# Portals_Controls.net
KiCad netlist of a schematic drawn in EAGLE
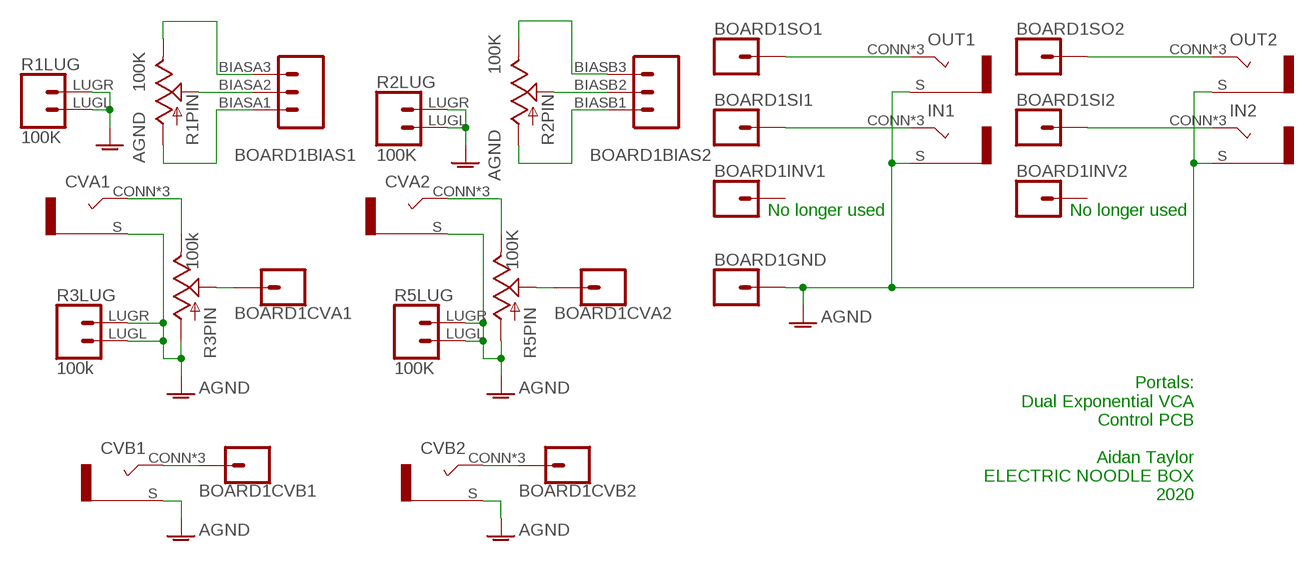
[diagram p0: schematic, sheet 1]

(export (version "E")
  (design (tool "Eeschema 10.0.6"))
  (components
    (comp (ref "BOARD1")
      (value "PORTALS_LINK")
      (footprint "eagle-import:PORTALS")
      (libsource (lib "eagle-import") (part "PORTALS_LINK"))
    )
    (comp (ref "CVA1")
      (value "COMBI-JACKCINCHNANA")
      (footprint "eagle-import:NEWCOMBOJACK_PANEL")
      (libsource (lib "eagle-import") (part "COMBI-JACKCINCHNANA"))
    )
    (comp (ref "CVA2")
      (value "COMBI-JACKCINCHNANA")
      (footprint "eagle-import:NEWCOMBOJACK_PANEL")
      (libsource (lib "eagle-import") (part "COMBI-JACKCINCHNANA"))
    )
    (comp (ref "CVB1")
      (value "COMBI-JACKCINCHNANA")
      (footprint "eagle-import:NEWCOMBOJACK_PANEL")
      (libsource (lib "eagle-import") (part "COMBI-JACKCINCHNANA"))
    )
    (comp (ref "CVB2")
      (value "COMBI-JACKCINCHNANA")
      (footprint "eagle-import:NEWCOMBOJACK_PANEL")
      (libsource (lib "eagle-import") (part "COMBI-JACKCINCHNANA"))
    )
    (comp (ref "IN1")
      (value "COMBI-JACKCINCHNANA")
      (footprint "eagle-import:NEWCOMBOJACK_PANEL")
      (libsource (lib "eagle-import") (part "COMBI-JACKCINCHNANA"))
    )
    (comp (ref "IN2")
      (value "COMBI-JACKCINCHNANA")
      (footprint "eagle-import:NEWCOMBOJACK_PANEL")
      (libsource (lib "eagle-import") (part "COMBI-JACKCINCHNANA"))
    )
    (comp (ref "OUT1")
      (value "COMBI-JACKCINCHNANA")
      (footprint "eagle-import:NEWCOMBOJACK_PANEL")
      (libsource (lib "eagle-import") (part "COMBI-JACKCINCHNANA"))
    )
    (comp (ref "OUT2")
      (value "COMBI-JACKCINCHNANA")
      (footprint "eagle-import:NEWCOMBOJACK_PANEL")
      (libsource (lib "eagle-import") (part "COMBI-JACKCINCHNANA"))
    )
    (comp (ref "R1")
      (value "100K")
      (footprint "eagle-import:ALPHA_RV09_9MMPOT")
      (libsource (lib "eagle-import") (part "POTENTIOMETER"))
    )
    (comp (ref "R2")
      (value "100K")
      (footprint "eagle-import:ALPHA_RV09_9MMPOT")
      (libsource (lib "eagle-import") (part "POTENTIOMETER"))
    )
    (comp (ref "R3")
      (value "100k")
      (footprint "eagle-import:ALPHA_RV09_9MMPOT")
      (libsource (lib "eagle-import") (part "POTENTIOMETER"))
    )
    (comp (ref "R5")
      (value "100K")
      (footprint "eagle-import:ALPHA_RV09_9MMPOT")
      (libsource (lib "eagle-import") (part "POTENTIOMETER"))
    )
  )
  (nets
    (net (code "1") (name "AGND") (class "Default")
      (node (ref "BOARD1") (pin "G1") (pinfunction "1_G1") (pintype "passive"))
      (node (ref "BOARD1") (pin "G2") (pinfunction "1_G2") (pintype "passive"))
      (node (ref "BOARD1") (pin "G3") (pinfunction "1_G3") (pintype "passive"))
      (node (ref "BOARD1") (pin "G4") (pinfunction "1_G4") (pintype "passive"))
      (node (ref "CVA1") (pin "S") (pinfunction "S_S") (pintype "passive"))
      (node (ref "CVA2") (pin "S") (pinfunction "S_S") (pintype "passive"))
      (node (ref "CVB1") (pin "S") (pinfunction "S_S") (pintype "passive"))
      (node (ref "CVB2") (pin "S") (pinfunction "S_S") (pintype "passive"))
      (node (ref "IN1") (pin "S") (pinfunction "S_S") (pintype "passive"))
      (node (ref "IN2") (pin "S") (pinfunction "S_S") (pintype "passive"))
      (node (ref "OUT1") (pin "S") (pinfunction "S_S") (pintype "passive"))
      (node (ref "OUT2") (pin "S") (pinfunction "S_S") (pintype "passive"))
      (node (ref "R1") (pin "LUGL") (pinfunction "1_LUGL") (pintype "passive"))
      (node (ref "R1") (pin "LUGR") (pinfunction "2_LUGR") (pintype "passive"))
      (node (ref "R2") (pin "LUGL") (pinfunction "1_LUGL") (pintype "passive"))
      (node (ref "R2") (pin "LUGR") (pinfunction "2_LUGR") (pintype "passive"))
      (node (ref "R3") (pin "C1") (pinfunction "A_C1") (pintype "passive"))
      (node (ref "R3") (pin "LUGL") (pinfunction "1_LUGL") (pintype "passive"))
      (node (ref "R3") (pin "LUGR") (pinfunction "2_LUGR") (pintype "passive"))
      (node (ref "R5") (pin "C1") (pinfunction "A_C1") (pintype "passive"))
      (node (ref "R5") (pin "LUGL") (pinfunction "1_LUGL") (pintype "passive"))
      (node (ref "R5") (pin "LUGR") (pinfunction "2_LUGR") (pintype "passive"))
    )
    (net (code "2") (name "Net-(BOARD1A-1)") (class "Default")
      (node (ref "BOARD1") (pin "BIASA1") (pinfunction "1_BIASA1") (pintype "passive"))
      (node (ref "R1") (pin "C1") (pinfunction "A_C1") (pintype "passive"))
    )
    (net (code "3") (name "Net-(BOARD1A-2)") (class "Default")
      (node (ref "BOARD1") (pin "BIASA2") (pinfunction "2_BIASA2") (pintype "passive"))
      (node (ref "R1") (pin "C2") (pinfunction "W_C2") (pintype "passive"))
    )
    (net (code "4") (name "Net-(BOARD1A-3)") (class "Default")
      (node (ref "BOARD1") (pin "BIASA3") (pinfunction "3_BIASA3") (pintype "passive"))
      (node (ref "R1") (pin "C3") (pinfunction "B_C3") (pintype "passive"))
    )
    (net (code "5") (name "Net-(BOARD1B-1)") (class "Default")
      (node (ref "BOARD1") (pin "BIASB1") (pinfunction "1_BIASB1") (pintype "passive"))
      (node (ref "R2") (pin "C1") (pinfunction "A_C1") (pintype "passive"))
    )
    (net (code "6") (name "Net-(BOARD1B-2)") (class "Default")
      (node (ref "BOARD1") (pin "BIASB2") (pinfunction "2_BIASB2") (pintype "passive"))
      (node (ref "R2") (pin "C2") (pinfunction "W_C2") (pintype "passive"))
    )
    (net (code "7") (name "Net-(BOARD1B-3)") (class "Default")
      (node (ref "BOARD1") (pin "BIASB3") (pinfunction "3_BIASB3") (pintype "passive"))
      (node (ref "R2") (pin "C3") (pinfunction "B_C3") (pintype "passive"))
    )
    (net (code "8") (name "Net-(BOARD1C-1)") (class "Default")
      (node (ref "BOARD1") (pin "CVA1") (pinfunction "1_CVA1") (pintype "passive"))
      (node (ref "R3") (pin "C2") (pinfunction "W_C2") (pintype "passive"))
    )
    (net (code "9") (name "Net-(BOARD1D-1)") (class "Default")
      (node (ref "BOARD1") (pin "CVIB1") (pinfunction "1_CVIB1") (pintype "passive"))
      (node (ref "R5") (pin "C2") (pinfunction "W_C2") (pintype "passive"))
    )
    (net (code "10") (name "Net-(BOARD1E-1)") (class "Default")
      (node (ref "BOARD1") (pin "CVA2") (pinfunction "1_CVA2") (pintype "passive"))
      (node (ref "CVB1") (pin "CONN") (pinfunction "T_CONN") (pintype "passive"))
      (node (ref "CVB1") (pin "T1") (pinfunction "T_T1") (pintype "passive"))
      (node (ref "CVB1") (pin "T2") (pinfunction "T_T2") (pintype "passive"))
    )
    (net (code "11") (name "Net-(BOARD1F-1)") (class "Default")
      (node (ref "BOARD1") (pin "CVIB2") (pinfunction "1_CVIB2") (pintype "passive"))
      (node (ref "CVB2") (pin "CONN") (pinfunction "T_CONN") (pintype "passive"))
      (node (ref "CVB2") (pin "T1") (pinfunction "T_T1") (pintype "passive"))
      (node (ref "CVB2") (pin "T2") (pinfunction "T_T2") (pintype "passive"))
    )
    (net (code "12") (name "Net-(BOARD1J-1)") (class "Default")
      (node (ref "BOARD1") (pin "SIA") (pinfunction "1_SIA") (pintype "passive"))
      (node (ref "IN1") (pin "CONN") (pinfunction "T_CONN") (pintype "passive"))
      (node (ref "IN1") (pin "T1") (pinfunction "T_T1") (pintype "passive"))
      (node (ref "IN1") (pin "T2") (pinfunction "T_T2") (pintype "passive"))
    )
    (net (code "13") (name "Net-(BOARD1K-1)") (class "Default")
      (node (ref "BOARD1") (pin "SIB") (pinfunction "1_SIB") (pintype "passive"))
      (node (ref "IN2") (pin "CONN") (pinfunction "T_CONN") (pintype "passive"))
      (node (ref "IN2") (pin "T1") (pinfunction "T_T1") (pintype "passive"))
      (node (ref "IN2") (pin "T2") (pinfunction "T_T2") (pintype "passive"))
    )
    (net (code "14") (name "Net-(BOARD1L-1)") (class "Default")
      (node (ref "BOARD1") (pin "SOA") (pinfunction "1_SOA") (pintype "passive"))
      (node (ref "OUT1") (pin "CONN") (pinfunction "T_CONN") (pintype "passive"))
      (node (ref "OUT1") (pin "T1") (pinfunction "T_T1") (pintype "passive"))
      (node (ref "OUT1") (pin "T2") (pinfunction "T_T2") (pintype "passive"))
    )
    (net (code "15") (name "Net-(BOARD1M-1)") (class "Default")
      (node (ref "BOARD1") (pin "SOB") (pinfunction "1_SOB") (pintype "passive"))
      (node (ref "OUT2") (pin "CONN") (pinfunction "T_CONN") (pintype "passive"))
      (node (ref "OUT2") (pin "T1") (pinfunction "T_T1") (pintype "passive"))
      (node (ref "OUT2") (pin "T2") (pinfunction "T_T2") (pintype "passive"))
    )
    (net (code "16") (name "Net-(R3B-B)") (class "Default")
      (node (ref "CVA1") (pin "CONN") (pinfunction "T_CONN") (pintype "passive"))
      (node (ref "CVA1") (pin "T1") (pinfunction "T_T1") (pintype "passive"))
      (node (ref "CVA1") (pin "T2") (pinfunction "T_T2") (pintype "passive"))
      (node (ref "R3") (pin "C3") (pinfunction "B_C3") (pintype "passive"))
    )
    (net (code "17") (name "Net-(R5B-B)") (class "Default")
      (node (ref "CVA2") (pin "CONN") (pinfunction "T_CONN") (pintype "passive"))
      (node (ref "CVA2") (pin "T1") (pinfunction "T_T1") (pintype "passive"))
      (node (ref "CVA2") (pin "T2") (pinfunction "T_T2") (pintype "passive"))
      (node (ref "R5") (pin "C3") (pinfunction "B_C3") (pintype "passive"))
    )
    (net (code "18") (name "unconnected-(BOARD1H-1-PadINVA)") (class "Default")
      (node (ref "BOARD1") (pin "INVA") (pinfunction "1_INVA") (pintype "passive"))
    )
    (net (code "19") (name "unconnected-(BOARD1I-1-PadINVB)") (class "Default")
      (node (ref "BOARD1") (pin "INVB") (pinfunction "1_INVB") (pintype "passive"))
    )
  )
)
